# Sheet1.net
KiCad netlist of a schematic drawn in Altium Designer
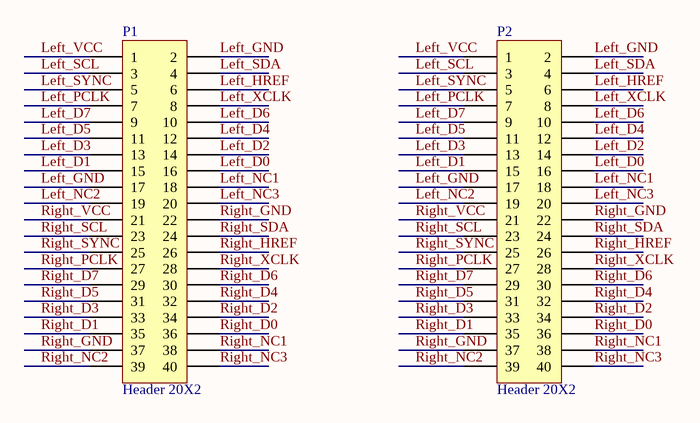
[diagram p0: Sheet1.SchDoc]

(export (version "E")
  (design (tool "Eeschema 10.0.6"))
  (components
    (comp (ref "P1")
      (value "Header 20X2")
      (footprint "FPC_40pin_05mm")
      (description "Header, 20-Pin, Dual row")
      (fields (field (name "PUBLISHER") "Altium Limited"))
      (libsource (lib "Miscellaneous Connectors") (part "Header 20X2"))
    )
    (comp (ref "P2")
      (value "Header 20X2")
      (footprint "FPC_40pin_05mm")
      (description "Header, 20-Pin, Dual row")
      (fields (field (name "PUBLISHER") "Altium Limited"))
      (libsource (lib "Miscellaneous Connectors") (part "Header 20X2"))
    )
  )
  (nets
    (net (code "1") (name "/Left_D0") (class "Default")
      (node (ref "P1") (pin "16") (pinfunction "16_16") (pintype "passive"))
      (node (ref "P2") (pin "16") (pinfunction "16_16") (pintype "passive"))
    )
    (net (code "2") (name "/Left_D1") (class "Default")
      (node (ref "P1") (pin "15") (pinfunction "15_15") (pintype "passive"))
      (node (ref "P2") (pin "15") (pinfunction "15_15") (pintype "passive"))
    )
    (net (code "3") (name "/Left_D2") (class "Default")
      (node (ref "P1") (pin "14") (pinfunction "14_14") (pintype "passive"))
      (node (ref "P2") (pin "14") (pinfunction "14_14") (pintype "passive"))
    )
    (net (code "4") (name "/Left_D3") (class "Default")
      (node (ref "P1") (pin "13") (pinfunction "13_13") (pintype "passive"))
      (node (ref "P2") (pin "13") (pinfunction "13_13") (pintype "passive"))
    )
    (net (code "5") (name "/Left_D4") (class "Default")
      (node (ref "P1") (pin "12") (pinfunction "12_12") (pintype "passive"))
      (node (ref "P2") (pin "12") (pinfunction "12_12") (pintype "passive"))
    )
    (net (code "6") (name "/Left_D5") (class "Default")
      (node (ref "P1") (pin "11") (pinfunction "11_11") (pintype "passive"))
      (node (ref "P2") (pin "11") (pinfunction "11_11") (pintype "passive"))
    )
    (net (code "7") (name "/Left_D6") (class "Default")
      (node (ref "P1") (pin "10") (pinfunction "10_10") (pintype "passive"))
      (node (ref "P2") (pin "10") (pinfunction "10_10") (pintype "passive"))
    )
    (net (code "8") (name "/Left_D7") (class "Default")
      (node (ref "P1") (pin "9") (pinfunction "9_9") (pintype "passive"))
      (node (ref "P2") (pin "9") (pinfunction "9_9") (pintype "passive"))
    )
    (net (code "9") (name "/Left_GND") (class "Default")
      (node (ref "P1") (pin "17") (pinfunction "17_17") (pintype "passive"))
      (node (ref "P1") (pin "2") (pinfunction "2_2") (pintype "passive"))
      (node (ref "P2") (pin "17") (pinfunction "17_17") (pintype "passive"))
      (node (ref "P2") (pin "2") (pinfunction "2_2") (pintype "passive"))
    )
    (net (code "10") (name "/Left_HREF") (class "Default")
      (node (ref "P1") (pin "6") (pinfunction "6_6") (pintype "passive"))
      (node (ref "P2") (pin "6") (pinfunction "6_6") (pintype "passive"))
    )
    (net (code "11") (name "/Left_NC1") (class "Default")
      (node (ref "P1") (pin "18") (pinfunction "18_18") (pintype "passive"))
      (node (ref "P2") (pin "18") (pinfunction "18_18") (pintype "passive"))
    )
    (net (code "12") (name "/Left_NC2") (class "Default")
      (node (ref "P1") (pin "19") (pinfunction "19_19") (pintype "passive"))
      (node (ref "P2") (pin "19") (pinfunction "19_19") (pintype "passive"))
    )
    (net (code "13") (name "/Left_NC3") (class "Default")
      (node (ref "P1") (pin "20") (pinfunction "20_20") (pintype "passive"))
      (node (ref "P2") (pin "20") (pinfunction "20_20") (pintype "passive"))
    )
    (net (code "14") (name "/Left_PCLK") (class "Default")
      (node (ref "P1") (pin "7") (pinfunction "7_7") (pintype "passive"))
      (node (ref "P2") (pin "7") (pinfunction "7_7") (pintype "passive"))
    )
    (net (code "15") (name "/Left_SCL") (class "Default")
      (node (ref "P1") (pin "3") (pinfunction "3_3") (pintype "passive"))
      (node (ref "P2") (pin "3") (pinfunction "3_3") (pintype "passive"))
    )
    (net (code "16") (name "/Left_SDA") (class "Default")
      (node (ref "P1") (pin "4") (pinfunction "4_4") (pintype "passive"))
      (node (ref "P2") (pin "4") (pinfunction "4_4") (pintype "passive"))
    )
    (net (code "17") (name "/Left_SYNC") (class "Default")
      (node (ref "P1") (pin "5") (pinfunction "5_5") (pintype "passive"))
      (node (ref "P2") (pin "5") (pinfunction "5_5") (pintype "passive"))
    )
    (net (code "18") (name "/Left_VCC") (class "Default")
      (node (ref "P1") (pin "1") (pinfunction "1_1") (pintype "passive"))
      (node (ref "P2") (pin "1") (pinfunction "1_1") (pintype "passive"))
    )
    (net (code "19") (name "/Left_XCLK") (class "Default")
      (node (ref "P1") (pin "8") (pinfunction "8_8") (pintype "passive"))
      (node (ref "P2") (pin "8") (pinfunction "8_8") (pintype "passive"))
    )
    (net (code "20") (name "/Right_D0") (class "Default")
      (node (ref "P1") (pin "36") (pinfunction "36_36") (pintype "passive"))
      (node (ref "P2") (pin "36") (pinfunction "36_36") (pintype "passive"))
    )
    (net (code "21") (name "/Right_D1") (class "Default")
      (node (ref "P1") (pin "35") (pinfunction "35_35") (pintype "passive"))
      (node (ref "P2") (pin "35") (pinfunction "35_35") (pintype "passive"))
    )
    (net (code "22") (name "/Right_D2") (class "Default")
      (node (ref "P1") (pin "34") (pinfunction "34_34") (pintype "passive"))
      (node (ref "P2") (pin "34") (pinfunction "34_34") (pintype "passive"))
    )
    (net (code "23") (name "/Right_D3") (class "Default")
      (node (ref "P1") (pin "33") (pinfunction "33_33") (pintype "passive"))
      (node (ref "P2") (pin "33") (pinfunction "33_33") (pintype "passive"))
    )
    (net (code "24") (name "/Right_D4") (class "Default")
      (node (ref "P1") (pin "32") (pinfunction "32_32") (pintype "passive"))
      (node (ref "P2") (pin "32") (pinfunction "32_32") (pintype "passive"))
    )
    (net (code "25") (name "/Right_D5") (class "Default")
      (node (ref "P1") (pin "31") (pinfunction "31_31") (pintype "passive"))
      (node (ref "P2") (pin "31") (pinfunction "31_31") (pintype "passive"))
    )
    (net (code "26") (name "/Right_D6") (class "Default")
      (node (ref "P1") (pin "30") (pinfunction "30_30") (pintype "passive"))
      (node (ref "P2") (pin "30") (pinfunction "30_30") (pintype "passive"))
    )
    (net (code "27") (name "/Right_D7") (class "Default")
      (node (ref "P1") (pin "29") (pinfunction "29_29") (pintype "passive"))
      (node (ref "P2") (pin "29") (pinfunction "29_29") (pintype "passive"))
    )
    (net (code "28") (name "/Right_GND") (class "Default")
      (node (ref "P1") (pin "22") (pinfunction "22_22") (pintype "passive"))
      (node (ref "P1") (pin "37") (pinfunction "37_37") (pintype "passive"))
      (node (ref "P2") (pin "22") (pinfunction "22_22") (pintype "passive"))
      (node (ref "P2") (pin "37") (pinfunction "37_37") (pintype "passive"))
    )
    (net (code "29") (name "/Right_HREF") (class "Default")
      (node (ref "P1") (pin "26") (pinfunction "26_26") (pintype "passive"))
      (node (ref "P2") (pin "26") (pinfunction "26_26") (pintype "passive"))
    )
    (net (code "30") (name "/Right_NC1") (class "Default")
      (node (ref "P1") (pin "38") (pinfunction "38_38") (pintype "passive"))
      (node (ref "P2") (pin "38") (pinfunction "38_38") (pintype "passive"))
    )
    (net (code "31") (name "/Right_NC2") (class "Default")
      (node (ref "P1") (pin "39") (pinfunction "39_39") (pintype "passive"))
      (node (ref "P2") (pin "39") (pinfunction "39_39") (pintype "passive"))
    )
    (net (code "32") (name "/Right_NC3") (class "Default")
      (node (ref "P1") (pin "40") (pinfunction "40_40") (pintype "passive"))
      (node (ref "P2") (pin "40") (pinfunction "40_40") (pintype "passive"))
    )
    (net (code "33") (name "/Right_PCLK") (class "Default")
      (node (ref "P1") (pin "27") (pinfunction "27_27") (pintype "passive"))
      (node (ref "P2") (pin "27") (pinfunction "27_27") (pintype "passive"))
    )
    (net (code "34") (name "/Right_SCL") (class "Default")
      (node (ref "P1") (pin "23") (pinfunction "23_23") (pintype "passive"))
      (node (ref "P2") (pin "23") (pinfunction "23_23") (pintype "passive"))
    )
    (net (code "35") (name "/Right_SDA") (class "Default")
      (node (ref "P1") (pin "24") (pinfunction "24_24") (pintype "passive"))
      (node (ref "P2") (pin "24") (pinfunction "24_24") (pintype "passive"))
    )
    (net (code "36") (name "/Right_SYNC") (class "Default")
      (node (ref "P1") (pin "25") (pinfunction "25_25") (pintype "passive"))
      (node (ref "P2") (pin "25") (pinfunction "25_25") (pintype "passive"))
    )
    (net (code "37") (name "/Right_VCC") (class "Default")
      (node (ref "P1") (pin "21") (pinfunction "21_21") (pintype "passive"))
      (node (ref "P2") (pin "21") (pinfunction "21_21") (pintype "passive"))
    )
    (net (code "38") (name "/Right_XCLK") (class "Default")
      (node (ref "P1") (pin "28") (pinfunction "28_28") (pintype "passive"))
      (node (ref "P2") (pin "28") (pinfunction "28_28") (pintype "passive"))
    )
  )
)
